# OUTPUT_SECTION.net
KiCad netlist of a schematic drawn in Altium Designer
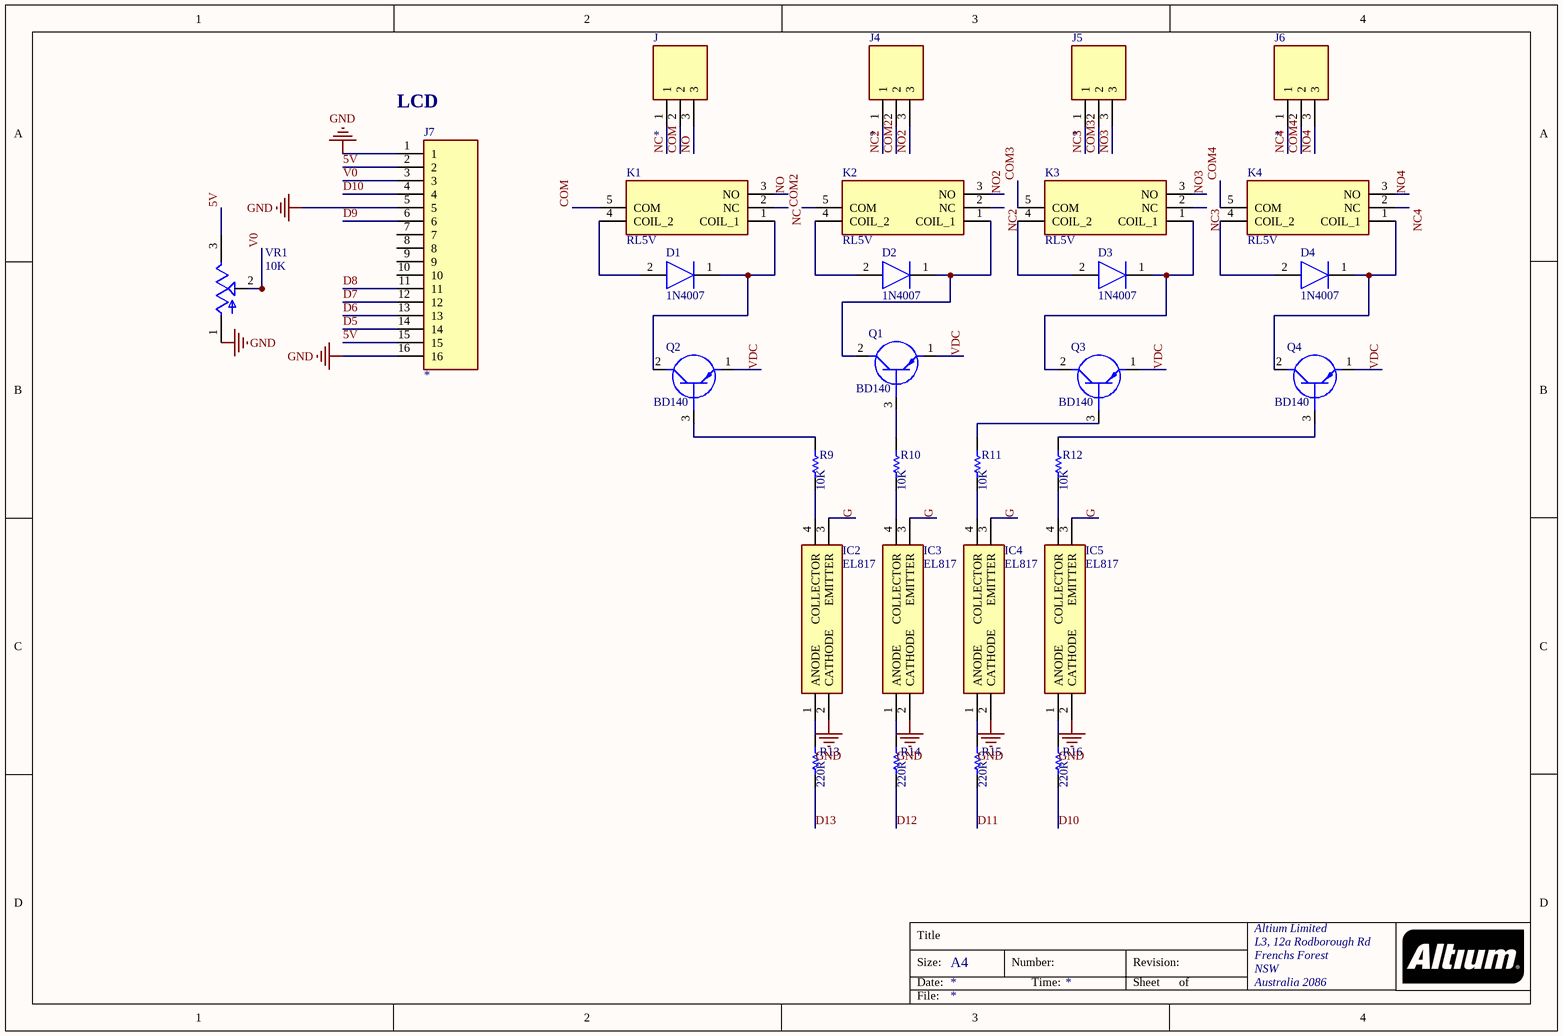
[diagram p0: OUTPUT SECTION.SchDoc]

(export (version "E")
  (design (tool "Eeschema 10.0.6"))
  (components
    (comp (ref "D1")
      (value "1N4007")
      (footprint "DIOAD1138W56L406D183")
      (description "Diode")
      (fields (field (name "MANUFACTURER_PART_NUMBER") "1N4678 (DO35)"))
      (libsource (lib "diode with 3d model") (part "1N4678__DO35_"))
    )
    (comp (ref "D2")
      (value "1N4007")
      (footprint "DIOAD1138W56L406D183")
      (description "Diode")
      (fields (field (name "MANUFACTURER_PART_NUMBER") "1N4678 (DO35)"))
      (libsource (lib "diode with 3d model") (part "1N4678__DO35_"))
    )
    (comp (ref "D3")
      (value "1N4007")
      (footprint "DIOAD1138W56L406D183")
      (description "Diode")
      (fields (field (name "MANUFACTURER_PART_NUMBER") "1N4678 (DO35)"))
      (libsource (lib "diode with 3d model") (part "1N4678__DO35_"))
    )
    (comp (ref "D4")
      (value "1N4007")
      (footprint "DIOAD1138W56L406D183")
      (description "Diode")
      (fields (field (name "MANUFACTURER_PART_NUMBER") "1N4678 (DO35)"))
      (libsource (lib "diode with 3d model") (part "1N4678__DO35_"))
    )
    (comp (ref "IC2")
      (value "EL817")
      (footprint "SamacSys:DIP762W60P254L458H480Q4N")
      (description "Integrated Circuit")
      (fields (field (name "MOUSER PART NUMBER") "638-817"))
      (libsource (lib "optocoupler 817") (part "EL817"))
    )
    (comp (ref "IC3")
      (value "EL817")
      (footprint "SamacSys:DIP762W60P254L458H480Q4N")
      (description "Integrated Circuit")
      (fields (field (name "MOUSER PART NUMBER") "638-817"))
      (libsource (lib "optocoupler 817") (part "EL817"))
    )
    (comp (ref "IC4")
      (value "EL817")
      (footprint "SamacSys:DIP762W60P254L458H480Q4N")
      (description "Integrated Circuit")
      (fields (field (name "MOUSER PART NUMBER") "638-817"))
      (libsource (lib "optocoupler 817") (part "EL817"))
    )
    (comp (ref "IC5")
      (value "EL817")
      (footprint "SamacSys:DIP762W60P254L458H480Q4N")
      (description "Integrated Circuit")
      (fields (field (name "MOUSER PART NUMBER") "638-817"))
      (libsource (lib "optocoupler 817") (part "EL817"))
    )
    (comp (ref "J")
      (value "1776118-3")
      (footprint "TE_1776118-3")
      (description "Conn Terminal Block F 3 POS 5mm Solder ST Thru-Hole Package")
      (fields (field (name "MF") "TE Connectivity") (field (name "COMMENT_1") "*"))
      (libsource (lib "3pin connector") (part "1776118-3"))
    )
    (comp (ref "J4")
      (value "1776118-3")
      (footprint "TE_1776118-3")
      (description "Conn Terminal Block F 3 POS 5mm Solder ST Thru-Hole Package")
      (fields (field (name "MF") "TE Connectivity") (field (name "COMMENT_1") "*"))
      (libsource (lib "3pin connector") (part "1776118-3"))
    )
    (comp (ref "J5")
      (value "1776118-3")
      (footprint "TE_1776118-3")
      (description "Conn Terminal Block F 3 POS 5mm Solder ST Thru-Hole Package")
      (fields (field (name "MF") "TE Connectivity") (field (name "COMMENT_1") "*"))
      (libsource (lib "3pin connector") (part "1776118-3"))
    )
    (comp (ref "J6")
      (value "1776118-3")
      (footprint "TE_1776118-3")
      (description "Conn Terminal Block F 3 POS 5mm Solder ST Thru-Hole Package")
      (fields (field (name "MF") "TE Connectivity") (field (name "COMMENT_1") "*"))
      (libsource (lib "3pin connector") (part "1776118-3"))
    )
    (comp (ref "J7")
      (value "1-826646-6")
      (footprint "TE_1-826646-6")
      (description "Connector Header Through Hole 16 position 0.100 (2.54mm)")
      (fields (field (name "MF") "TE Connectivity") (field (name "COMMENT_1") "*"))
      (libsource (lib "LCD16X2") (part "1-826646-6"))
    )
    (comp (ref "K1")
      (value "RL5V")
      (footprint "SamacSys:0476618")
      (description "Relay or Contactor")
      (fields (field (name "MANUFACTURER_PART_NUMBER") "0476618"))
      (libsource (lib "relay 5 pin") (part "0476618"))
    )
    (comp (ref "K2")
      (value "RL5V")
      (footprint "SamacSys:0476618")
      (description "Relay or Contactor")
      (fields (field (name "MANUFACTURER_PART_NUMBER") "0476618"))
      (libsource (lib "relay 5 pin") (part "0476618"))
    )
    (comp (ref "K3")
      (value "RL5V")
      (footprint "SamacSys:0476618")
      (description "Relay or Contactor")
      (fields (field (name "MANUFACTURER_PART_NUMBER") "0476618"))
      (libsource (lib "relay 5 pin") (part "0476618"))
    )
    (comp (ref "K4")
      (value "RL5V")
      (footprint "SamacSys:0476618")
      (description "Relay or Contactor")
      (fields (field (name "MANUFACTURER_PART_NUMBER") "0476618"))
      (libsource (lib "relay 5 pin") (part "0476618"))
    )
    (comp (ref "Q1")
      (value "BD140")
      (footprint "TO229P345X800X1460-3P")
      (description "Transistor BJT PNP")
      (fields
        (field (name "MANUFACTURER_PART_NUMBER") "BD14010STU")
        (field (name "MOUSER PART NUMBER") "512-BD14010STU")
      )
      (libsource (lib "BD140 pnp transistor") (part "BD14010STU"))
    )
    (comp (ref "Q2")
      (value "BD140")
      (footprint "TO229P345X800X1460-3P")
      (description "Transistor BJT PNP")
      (fields
        (field (name "MANUFACTURER_PART_NUMBER") "BD14010STU")
        (field (name "MOUSER PART NUMBER") "512-BD14010STU")
      )
      (libsource (lib "BD140 pnp transistor") (part "BD14010STU"))
    )
    (comp (ref "Q3")
      (value "BD140")
      (footprint "TO229P345X800X1460-3P")
      (description "Transistor BJT PNP")
      (fields
        (field (name "MANUFACTURER_PART_NUMBER") "BD14010STU")
        (field (name "MOUSER PART NUMBER") "512-BD14010STU")
      )
      (libsource (lib "BD140 pnp transistor") (part "BD14010STU"))
    )
    (comp (ref "Q4")
      (value "BD140")
      (footprint "TO229P345X800X1460-3P")
      (description "Transistor BJT PNP")
      (fields
        (field (name "MANUFACTURER_PART_NUMBER") "BD14010STU")
        (field (name "MOUSER PART NUMBER") "512-BD14010STU")
      )
      (libsource (lib "BD140 pnp transistor") (part "BD14010STU"))
    )
    (comp (ref "R9")
      (value "10K")
      (footprint "AXIAL-0.5")
      (description "Semiconductor Resistor")
      (fields (field (name "PUBLISHER") "Altium Limited"))
      (libsource (lib "Miscellaneous Devices") (part "Res Semi"))
    )
    (comp (ref "R10")
      (value "10K")
      (footprint "AXIAL-0.5")
      (description "Semiconductor Resistor")
      (fields (field (name "PUBLISHER") "Altium Limited"))
      (libsource (lib "Miscellaneous Devices") (part "Res Semi"))
    )
    (comp (ref "R11")
      (value "10K")
      (footprint "AXIAL-0.5")
      (description "Semiconductor Resistor")
      (fields (field (name "PUBLISHER") "Altium Limited"))
      (libsource (lib "Miscellaneous Devices") (part "Res Semi"))
    )
    (comp (ref "R12")
      (value "10K")
      (footprint "AXIAL-0.5")
      (description "Semiconductor Resistor")
      (fields (field (name "PUBLISHER") "Altium Limited"))
      (libsource (lib "Miscellaneous Devices") (part "Res Semi"))
    )
    (comp (ref "R13")
      (value "220R")
      (footprint "AXIAL-0.5")
      (description "Semiconductor Resistor")
      (fields (field (name "PUBLISHER") "Altium Limited"))
      (libsource (lib "Miscellaneous Devices") (part "Res Semi"))
    )
    (comp (ref "R14")
      (value "220R")
      (footprint "AXIAL-0.5")
      (description "Semiconductor Resistor")
      (fields (field (name "PUBLISHER") "Altium Limited"))
      (libsource (lib "Miscellaneous Devices") (part "Res Semi"))
    )
    (comp (ref "R15")
      (value "220R")
      (footprint "AXIAL-0.5")
      (description "Semiconductor Resistor")
      (fields (field (name "PUBLISHER") "Altium Limited"))
      (libsource (lib "Miscellaneous Devices") (part "Res Semi"))
    )
    (comp (ref "R16")
      (value "220R")
      (footprint "AXIAL-0.5")
      (description "Semiconductor Resistor")
      (fields (field (name "PUBLISHER") "Altium Limited"))
      (libsource (lib "Miscellaneous Devices") (part "Res Semi"))
    )
    (comp (ref "VR1")
      (value "10K")
      (footprint "TRIM_3362P-1-105")
      (description "1 MOhms 0.5W, 1/2W PC Pins Through Hole Trimmer Potentiometer Cermet 1 Turn Top Adjustment")
      (fields (field (name "MF") "Bourns") (field (name "MP") "3362P-1-105"))
      (libsource (lib "POT res 3D") (part "3362P-1-105"))
    )
  )
  (nets
    (net (code "1") (name "/5V") (class "Default")
      (node (ref "J7") (pin "15") (pinfunction "15_15") (pintype "passive"))
      (node (ref "J7") (pin "2") (pinfunction "2_2") (pintype "passive"))
      (node (ref "VR1") (pin "3") (pinfunction "CW_3") (pintype "passive"))
    )
    (net (code "2") (name "/COM") (class "Default")
      (node (ref "J") (pin "2") (pinfunction "2_2") (pintype "passive"))
      (node (ref "K1") (pin "5") (pinfunction "COM_5") (pintype "passive"))
    )
    (net (code "3") (name "/COM2") (class "Default")
      (node (ref "J4") (pin "2") (pinfunction "2_2") (pintype "passive"))
      (node (ref "K2") (pin "5") (pinfunction "COM_5") (pintype "passive"))
    )
    (net (code "4") (name "/COM3") (class "Default")
      (node (ref "J5") (pin "2") (pinfunction "2_2") (pintype "passive"))
      (node (ref "K3") (pin "5") (pinfunction "COM_5") (pintype "passive"))
    )
    (net (code "5") (name "/COM4") (class "Default")
      (node (ref "J6") (pin "2") (pinfunction "2_2") (pintype "passive"))
      (node (ref "K4") (pin "5") (pinfunction "COM_5") (pintype "passive"))
    )
    (net (code "6") (name "/D5") (class "Default")
      (node (ref "J7") (pin "14") (pinfunction "14_14") (pintype "passive"))
    )
    (net (code "7") (name "/D6") (class "Default")
      (node (ref "J7") (pin "13") (pinfunction "13_13") (pintype "passive"))
    )
    (net (code "8") (name "/D7") (class "Default")
      (node (ref "J7") (pin "12") (pinfunction "12_12") (pintype "passive"))
    )
    (net (code "9") (name "/D8") (class "Default")
      (node (ref "J7") (pin "11") (pinfunction "11_11") (pintype "passive"))
    )
    (net (code "10") (name "/D9") (class "Default")
      (node (ref "J7") (pin "6") (pinfunction "6_6") (pintype "passive"))
    )
    (net (code "11") (name "/D10") (class "Default")
      (node (ref "J7") (pin "4") (pinfunction "4_4") (pintype "passive"))
      (node (ref "R16") (pin "1") (pinfunction "1_1") (pintype "passive"))
    )
    (net (code "12") (name "/D11") (class "Default")
      (node (ref "R15") (pin "1") (pinfunction "1_1") (pintype "passive"))
    )
    (net (code "13") (name "/D12") (class "Default")
      (node (ref "R14") (pin "1") (pinfunction "1_1") (pintype "passive"))
    )
    (net (code "14") (name "/D13") (class "Default")
      (node (ref "R13") (pin "1") (pinfunction "1_1") (pintype "passive"))
    )
    (net (code "15") (name "/G") (class "Default")
      (node (ref "IC2") (pin "3") (pinfunction "EMITTER_3") (pintype "passive"))
      (node (ref "IC3") (pin "3") (pinfunction "EMITTER_3") (pintype "passive"))
      (node (ref "IC4") (pin "3") (pinfunction "EMITTER_3") (pintype "passive"))
      (node (ref "IC5") (pin "3") (pinfunction "EMITTER_3") (pintype "passive"))
    )
    (net (code "16") (name "/NC") (class "Default")
      (node (ref "J") (pin "1") (pinfunction "1_1") (pintype "passive"))
      (node (ref "K1") (pin "2") (pinfunction "NC_2") (pintype "passive"))
    )
    (net (code "17") (name "/NC2") (class "Default")
      (node (ref "J4") (pin "1") (pinfunction "1_1") (pintype "passive"))
      (node (ref "K2") (pin "2") (pinfunction "NC_2") (pintype "passive"))
    )
    (net (code "18") (name "/NC3") (class "Default")
      (node (ref "J5") (pin "1") (pinfunction "1_1") (pintype "passive"))
      (node (ref "K3") (pin "2") (pinfunction "NC_2") (pintype "passive"))
    )
    (net (code "19") (name "/NC4") (class "Default")
      (node (ref "J6") (pin "1") (pinfunction "1_1") (pintype "passive"))
      (node (ref "K4") (pin "2") (pinfunction "NC_2") (pintype "passive"))
    )
    (net (code "20") (name "/NO") (class "Default")
      (node (ref "J") (pin "3") (pinfunction "3_3") (pintype "passive"))
      (node (ref "K1") (pin "3") (pinfunction "NO_3") (pintype "passive"))
    )
    (net (code "21") (name "/NO2") (class "Default")
      (node (ref "J4") (pin "3") (pinfunction "3_3") (pintype "passive"))
      (node (ref "K2") (pin "3") (pinfunction "NO_3") (pintype "passive"))
    )
    (net (code "22") (name "/NO3") (class "Default")
      (node (ref "J5") (pin "3") (pinfunction "3_3") (pintype "passive"))
      (node (ref "K3") (pin "3") (pinfunction "NO_3") (pintype "passive"))
    )
    (net (code "23") (name "/NO4") (class "Default")
      (node (ref "J6") (pin "3") (pinfunction "3_3") (pintype "passive"))
      (node (ref "K4") (pin "3") (pinfunction "NO_3") (pintype "passive"))
    )
    (net (code "24") (name "/V0") (class "Default")
      (node (ref "J7") (pin "3") (pinfunction "3_3") (pintype "passive"))
      (node (ref "VR1") (pin "2") (pinfunction "WIPER_2") (pintype "passive"))
    )
    (net (code "25") (name "/VDC") (class "Default")
      (node (ref "Q1") (pin "1") (pinfunction "E_1") (pintype "passive"))
      (node (ref "Q2") (pin "1") (pinfunction "E_1") (pintype "passive"))
      (node (ref "Q3") (pin "1") (pinfunction "E_1") (pintype "passive"))
      (node (ref "Q4") (pin "1") (pinfunction "E_1") (pintype "passive"))
    )
    (net (code "26") (name "GND") (class "Default")
      (node (ref "IC2") (pin "2") (pinfunction "CATHODE_2") (pintype "passive"))
      (node (ref "IC3") (pin "2") (pinfunction "CATHODE_2") (pintype "passive"))
      (node (ref "IC4") (pin "2") (pinfunction "CATHODE_2") (pintype "passive"))
      (node (ref "IC5") (pin "2") (pinfunction "CATHODE_2") (pintype "passive"))
      (node (ref "J7") (pin "1") (pinfunction "1_1") (pintype "passive"))
      (node (ref "J7") (pin "16") (pinfunction "16_16") (pintype "passive"))
      (node (ref "J7") (pin "5") (pinfunction "5_5") (pintype "passive"))
      (node (ref "VR1") (pin "1") (pinfunction "CCW_1") (pintype "passive"))
    )
    (net (code "27") (name "Net-(D1-A)") (class "Default")
      (node (ref "D1") (pin "2") (pinfunction "A_2") (pintype "passive"))
      (node (ref "K1") (pin "4") (pinfunction "COIL_2_4") (pintype "passive"))
    )
    (net (code "28") (name "Net-(D1-K)") (class "Default")
      (node (ref "D1") (pin "1") (pinfunction "K_1") (pintype "passive"))
      (node (ref "K1") (pin "1") (pinfunction "COIL_1_1") (pintype "passive"))
      (node (ref "Q2") (pin "2") (pinfunction "C_2") (pintype "passive"))
    )
    (net (code "29") (name "Net-(D2-A)") (class "Default")
      (node (ref "D2") (pin "2") (pinfunction "A_2") (pintype "passive"))
      (node (ref "K2") (pin "4") (pinfunction "COIL_2_4") (pintype "passive"))
    )
    (net (code "30") (name "Net-(D2-K)") (class "Default")
      (node (ref "D2") (pin "1") (pinfunction "K_1") (pintype "passive"))
      (node (ref "K2") (pin "1") (pinfunction "COIL_1_1") (pintype "passive"))
      (node (ref "Q1") (pin "2") (pinfunction "C_2") (pintype "passive"))
    )
    (net (code "31") (name "Net-(D3-A)") (class "Default")
      (node (ref "D3") (pin "2") (pinfunction "A_2") (pintype "passive"))
      (node (ref "K3") (pin "4") (pinfunction "COIL_2_4") (pintype "passive"))
    )
    (net (code "32") (name "Net-(D3-K)") (class "Default")
      (node (ref "D3") (pin "1") (pinfunction "K_1") (pintype "passive"))
      (node (ref "K3") (pin "1") (pinfunction "COIL_1_1") (pintype "passive"))
      (node (ref "Q3") (pin "2") (pinfunction "C_2") (pintype "passive"))
    )
    (net (code "33") (name "Net-(D4-A)") (class "Default")
      (node (ref "D4") (pin "2") (pinfunction "A_2") (pintype "passive"))
      (node (ref "K4") (pin "4") (pinfunction "COIL_2_4") (pintype "passive"))
    )
    (net (code "34") (name "Net-(D4-K)") (class "Default")
      (node (ref "D4") (pin "1") (pinfunction "K_1") (pintype "passive"))
      (node (ref "K4") (pin "1") (pinfunction "COIL_1_1") (pintype "passive"))
      (node (ref "Q4") (pin "2") (pinfunction "C_2") (pintype "passive"))
    )
    (net (code "35") (name "Net-(IC2-ANODE)") (class "Default")
      (node (ref "IC2") (pin "1") (pinfunction "ANODE_1") (pintype "passive"))
      (node (ref "R13") (pin "2") (pinfunction "2_2") (pintype "passive"))
    )
    (net (code "36") (name "Net-(IC2-COLLECTOR)") (class "Default")
      (node (ref "IC2") (pin "4") (pinfunction "COLLECTOR_4") (pintype "passive"))
      (node (ref "R9") (pin "1") (pinfunction "1_1") (pintype "passive"))
    )
    (net (code "37") (name "Net-(IC3-ANODE)") (class "Default")
      (node (ref "IC3") (pin "1") (pinfunction "ANODE_1") (pintype "passive"))
      (node (ref "R14") (pin "2") (pinfunction "2_2") (pintype "passive"))
    )
    (net (code "38") (name "Net-(IC3-COLLECTOR)") (class "Default")
      (node (ref "IC3") (pin "4") (pinfunction "COLLECTOR_4") (pintype "passive"))
      (node (ref "R10") (pin "1") (pinfunction "1_1") (pintype "passive"))
    )
    (net (code "39") (name "Net-(IC4-ANODE)") (class "Default")
      (node (ref "IC4") (pin "1") (pinfunction "ANODE_1") (pintype "passive"))
      (node (ref "R15") (pin "2") (pinfunction "2_2") (pintype "passive"))
    )
    (net (code "40") (name "Net-(IC4-COLLECTOR)") (class "Default")
      (node (ref "IC4") (pin "4") (pinfunction "COLLECTOR_4") (pintype "passive"))
      (node (ref "R11") (pin "1") (pinfunction "1_1") (pintype "passive"))
    )
    (net (code "41") (name "Net-(IC5-ANODE)") (class "Default")
      (node (ref "IC5") (pin "1") (pinfunction "ANODE_1") (pintype "passive"))
      (node (ref "R16") (pin "2") (pinfunction "2_2") (pintype "passive"))
    )
    (net (code "42") (name "Net-(IC5-COLLECTOR)") (class "Default")
      (node (ref "IC5") (pin "4") (pinfunction "COLLECTOR_4") (pintype "passive"))
      (node (ref "R12") (pin "1") (pinfunction "1_1") (pintype "passive"))
    )
    (net (code "43") (name "Net-(Q1-B)") (class "Default")
      (node (ref "Q1") (pin "3") (pinfunction "B_3") (pintype "passive"))
      (node (ref "R10") (pin "2") (pinfunction "2_2") (pintype "passive"))
    )
    (net (code "44") (name "Net-(Q2-B)") (class "Default")
      (node (ref "Q2") (pin "3") (pinfunction "B_3") (pintype "passive"))
      (node (ref "R9") (pin "2") (pinfunction "2_2") (pintype "passive"))
    )
    (net (code "45") (name "Net-(Q3-B)") (class "Default")
      (node (ref "Q3") (pin "3") (pinfunction "B_3") (pintype "passive"))
      (node (ref "R11") (pin "2") (pinfunction "2_2") (pintype "passive"))
    )
    (net (code "46") (name "Net-(Q4-B)") (class "Default")
      (node (ref "Q4") (pin "3") (pinfunction "B_3") (pintype "passive"))
      (node (ref "R12") (pin "2") (pinfunction "2_2") (pintype "passive"))
    )
    (net (code "47") (name "unconnected-(J7-Pad7)") (class "Default")
      (node (ref "J7") (pin "7") (pinfunction "7_7") (pintype "passive"))
    )
    (net (code "48") (name "unconnected-(J7-Pad8)") (class "Default")
      (node (ref "J7") (pin "8") (pinfunction "8_8") (pintype "passive"))
    )
    (net (code "49") (name "unconnected-(J7-Pad9)") (class "Default")
      (node (ref "J7") (pin "9") (pinfunction "9_9") (pintype "passive"))
    )
    (net (code "50") (name "unconnected-(J7-Pad10)") (class "Default")
      (node (ref "J7") (pin "10") (pinfunction "10_10") (pintype "passive"))
    )
  )
)
